# Xbee_shield.net
KiCad netlist of a schematic drawn in EAGLE
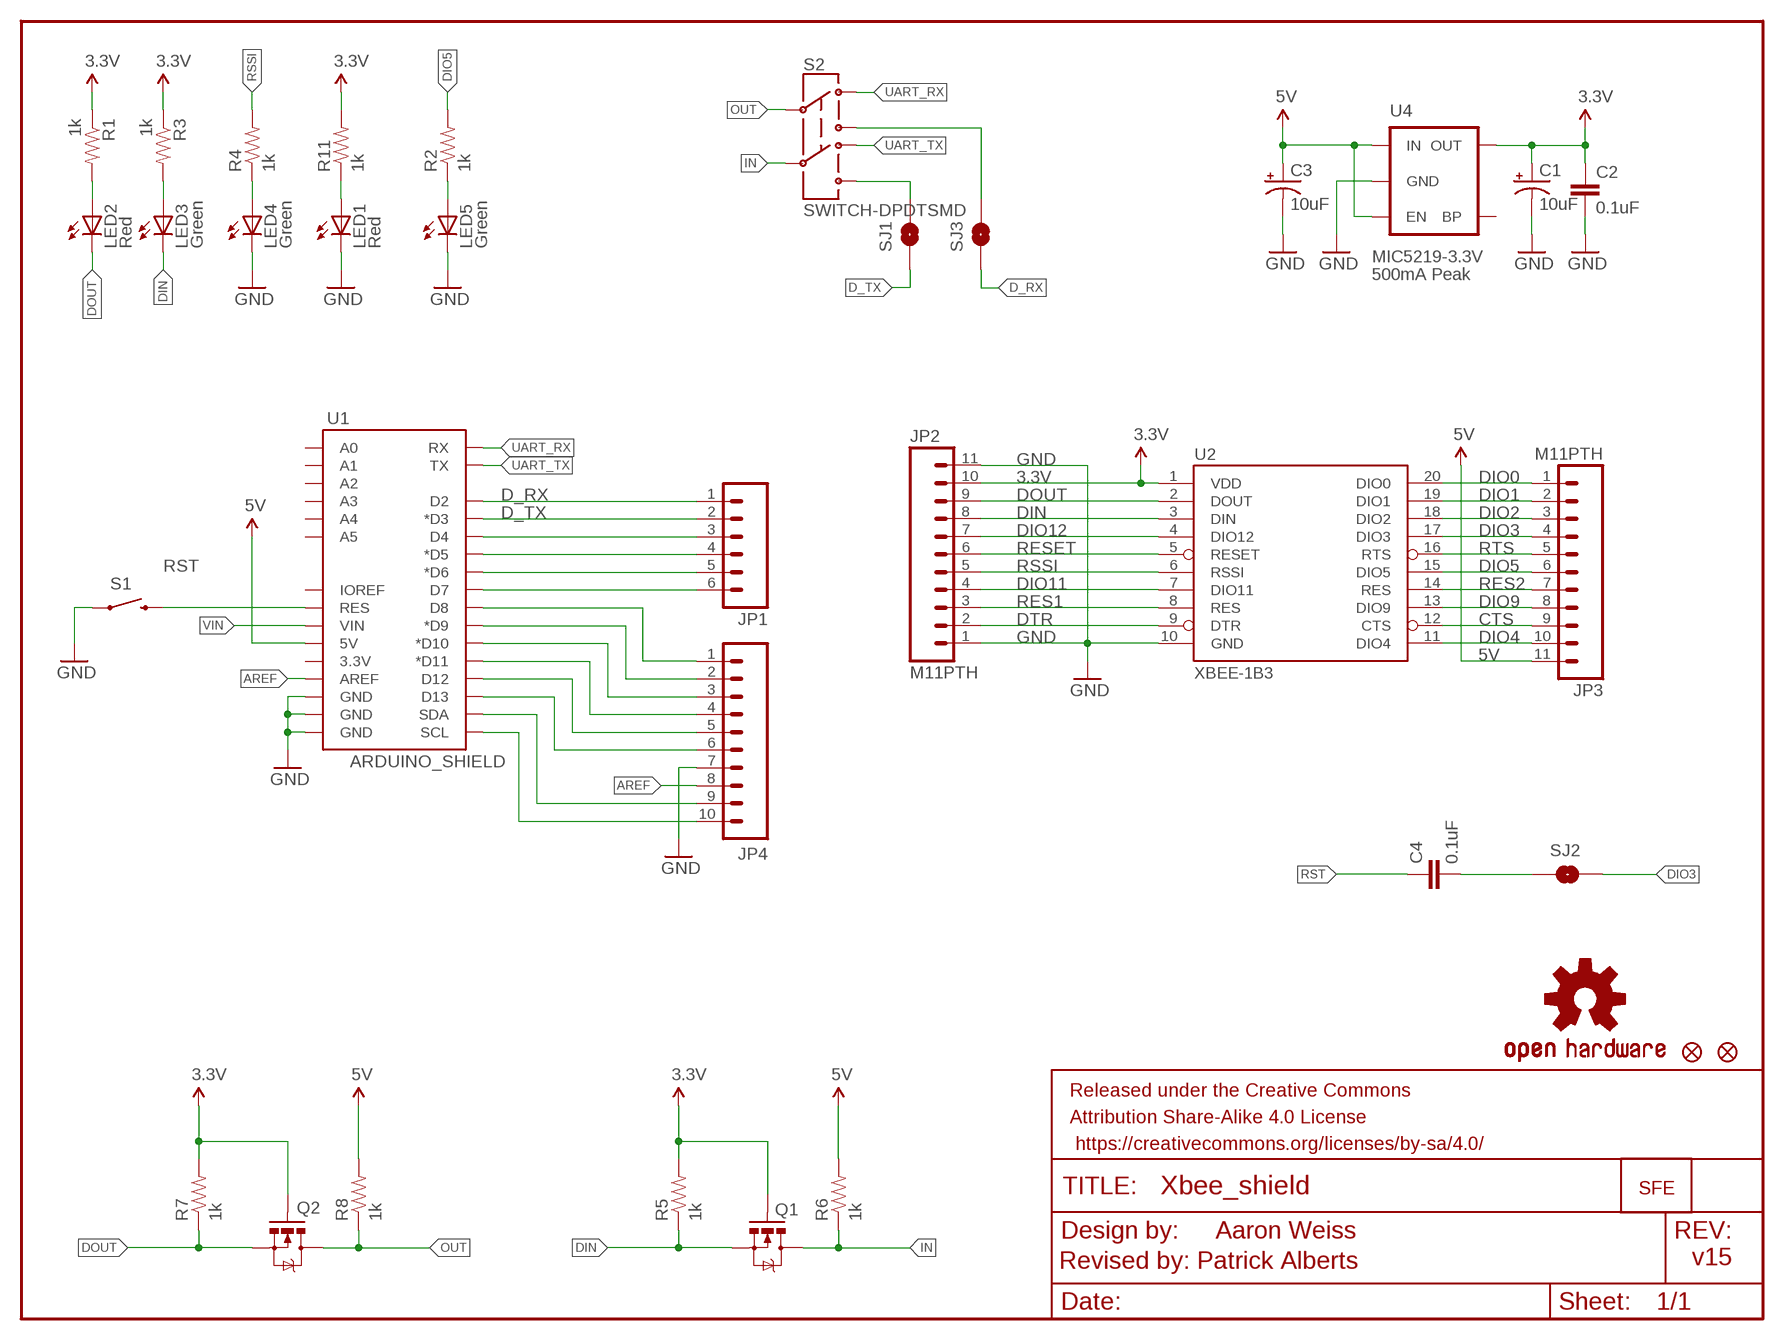
[diagram p0: schematic, sheet 1]

(export (version "E")
  (design (tool "Eeschema 10.0.6"))
  (components
    (comp (ref "C1")
      (value "10uF")
      (footprint "eagle-import:EIA3216")
      (libsource (lib "eagle-import") (part "CAP_POL1206"))
    )
    (comp (ref "C2")
      (value "0.1uF")
      (footprint "eagle-import:0603-CAP")
      (libsource (lib "eagle-import") (part "0.1UF-25V(+80/-20%)(0603)"))
    )
    (comp (ref "C3")
      (value "10uF")
      (footprint "eagle-import:EIA3216")
      (libsource (lib "eagle-import") (part "CAP_POL1206"))
    )
    (comp (ref "C4")
      (value "0.1uF")
      (footprint "eagle-import:0603-CAP")
      (libsource (lib "eagle-import") (part "0.1UF-25V(+80/-20%)(0603)"))
    )
    (comp (ref "FRAME1")
      (value "FRAME-LETTER")
      (footprint "eagle-import:CREATIVE_COMMONS")
      (libsource (lib "eagle-import") (part "FRAME-LETTER"))
    )
    (comp (ref "JP1")
      (value "M06SIP")
      (footprint "eagle-import:1X06")
      (libsource (lib "eagle-import") (part "M06SIP"))
    )
    (comp (ref "JP2")
      (value "M11PTH")
      (footprint "eagle-import:1X11")
      (libsource (lib "eagle-import") (part "M11PTH"))
    )
    (comp (ref "JP3")
      (value "M11PTH")
      (footprint "eagle-import:1X11")
      (libsource (lib "eagle-import") (part "M11PTH"))
    )
    (comp (ref "JP4")
      (value "M10\"")
      (footprint "eagle-import:1X10")
      (libsource (lib "eagle-import") (part "M10{dblquote}"))
    )
    (comp (ref "JP5")
      (value "FIDUCIAL1X2")
      (footprint "eagle-import:FIDUCIAL-1X2")
      (libsource (lib "eagle-import") (part "FIDUCIAL1X2"))
    )
    (comp (ref "JP6")
      (value "FIDUCIAL1X2")
      (footprint "eagle-import:FIDUCIAL-1X2")
      (libsource (lib "eagle-import") (part "FIDUCIAL1X2"))
    )
    (comp (ref "JP7")
      (value "LOGO-SFENEW")
      (footprint "eagle-import:SFE-NEW-WEBLOGO")
      (libsource (lib "eagle-import") (part "LOGO-SFENEW"))
    )
    (comp (ref "LED1")
      (value "Red")
      (footprint "eagle-import:LED-0603")
      (libsource (lib "eagle-import") (part "LED-RED0603"))
    )
    (comp (ref "LED2")
      (value "Red")
      (footprint "eagle-import:LED-0603")
      (libsource (lib "eagle-import") (part "LED-RED0603"))
    )
    (comp (ref "LED3")
      (value "Green")
      (footprint "eagle-import:LED-0603")
      (libsource (lib "eagle-import") (part "LED-GREEN0603"))
    )
    (comp (ref "LED4")
      (value "Green")
      (footprint "eagle-import:LED-0603")
      (libsource (lib "eagle-import") (part "LED-GREEN0603"))
    )
    (comp (ref "LED5")
      (value "Green")
      (footprint "eagle-import:LED-0603")
      (libsource (lib "eagle-import") (part "LED-GREEN0603"))
    )
    (comp (ref "Q1")
      (value "MOSFET-NCHANNELSMD")
      (footprint "eagle-import:SOT23-3")
      (libsource (lib "eagle-import") (part "MOSFET-NCHANNELSMD"))
    )
    (comp (ref "Q2")
      (value "MOSFET-NCHANNELSMD")
      (footprint "eagle-import:SOT23-3")
      (libsource (lib "eagle-import") (part "MOSFET-NCHANNELSMD"))
    )
    (comp (ref "R1")
      (value "1k")
      (footprint "eagle-import:0603-RES")
      (libsource (lib "eagle-import") (part "1KOHM1/10W1%(0603)"))
    )
    (comp (ref "R2")
      (value "1k")
      (footprint "eagle-import:0603-RES")
      (libsource (lib "eagle-import") (part "1KOHM1/10W1%(0603)"))
    )
    (comp (ref "R3")
      (value "1k")
      (footprint "eagle-import:0603-RES")
      (libsource (lib "eagle-import") (part "1KOHM1/10W1%(0603)"))
    )
    (comp (ref "R4")
      (value "1k")
      (footprint "eagle-import:0603-RES")
      (libsource (lib "eagle-import") (part "1KOHM1/10W1%(0603)"))
    )
    (comp (ref "R5")
      (value "1k")
      (footprint "eagle-import:0603-RES")
      (libsource (lib "eagle-import") (part "1KOHM1/10W1%(0603)"))
    )
    (comp (ref "R6")
      (value "1k")
      (footprint "eagle-import:0603-RES")
      (libsource (lib "eagle-import") (part "1KOHM1/10W1%(0603)"))
    )
    (comp (ref "R7")
      (value "1k")
      (footprint "eagle-import:0603-RES")
      (libsource (lib "eagle-import") (part "1KOHM1/10W1%(0603)"))
    )
    (comp (ref "R8")
      (value "1k")
      (footprint "eagle-import:0603-RES")
      (libsource (lib "eagle-import") (part "1KOHM1/10W1%(0603)"))
    )
    (comp (ref "R11")
      (value "1k")
      (footprint "eagle-import:0603-RES")
      (libsource (lib "eagle-import") (part "1KOHM1/10W1%(0603)"))
    )
    (comp (ref "S1")
      (value "SWITCH-MOMENTARY-2SMD")
      (footprint "eagle-import:TACTILE_SWITCH_SMD")
      (libsource (lib "eagle-import") (part "SWITCH-MOMENTARY-2SMD"))
    )
    (comp (ref "S2")
      (value "SWITCH-DPDTSMD")
      (footprint "eagle-import:AYZ0202")
      (libsource (lib "eagle-import") (part "SWITCH-DPDTSMD"))
    )
    (comp (ref "SJ1")
      (value "D_TX")
      (footprint "eagle-import:SJ_2S")
      (libsource (lib "eagle-import") (part "SOLDERJUMPERNC"))
    )
    (comp (ref "SJ2")
      (value "SOLDERJUMPERTRACE")
      (footprint "eagle-import:SJ_2S-TRACE")
      (libsource (lib "eagle-import") (part "SOLDERJUMPERTRACE"))
    )
    (comp (ref "SJ3")
      (value "D_RX")
      (footprint "eagle-import:SJ_2S")
      (libsource (lib "eagle-import") (part "SOLDERJUMPERNC"))
    )
    (comp (ref "U$8")
      (value "OSHW-LOGOS")
      (footprint "eagle-import:OSHW-LOGO-S")
      (libsource (lib "eagle-import") (part "OSHW-LOGOS"))
    )
    (comp (ref "U1")
      (value "ARDUINO_SHIELD")
      (footprint "eagle-import:UNO_R3_SHIELD")
      (libsource (lib "eagle-import") (part "ARDUINO_R3_SHIELD"))
    )
    (comp (ref "U2")
      (value "XBEE-1B3")
      (footprint "eagle-import:XBEE-SMD")
      (libsource (lib "eagle-import") (part "XBEE-1B3"))
    )
    (comp (ref "U4")
      (value "V_REG_LDOSMD")
      (footprint "eagle-import:SOT23-5")
      (libsource (lib "eagle-import") (part "V_REG_LDOSMD"))
    )
  )
  (nets
    (net (code "1") (name "/CTS") (class "Default")
      (node (ref "JP3") (pin "9") (pinfunction "9_9") (pintype "passive"))
      (node (ref "U2") (pin "12") (pinfunction "CTS_12") (pintype "output"))
    )
    (net (code "2") (name "/DIO0") (class "Default")
      (node (ref "JP3") (pin "1") (pinfunction "1_1") (pintype "passive"))
      (node (ref "U2") (pin "20") (pinfunction "DIO0_20") (pintype "bidirectional"))
    )
    (net (code "3") (name "/DIO1") (class "Default")
      (node (ref "JP3") (pin "2") (pinfunction "2_2") (pintype "passive"))
      (node (ref "U2") (pin "19") (pinfunction "DIO1_19") (pintype "bidirectional"))
    )
    (net (code "4") (name "/DIO2") (class "Default")
      (node (ref "JP3") (pin "3") (pinfunction "3_3") (pintype "passive"))
      (node (ref "U2") (pin "18") (pinfunction "DIO2_18") (pintype "bidirectional"))
    )
    (net (code "5") (name "/DIO4") (class "Default")
      (node (ref "JP3") (pin "10") (pinfunction "10_10") (pintype "passive"))
      (node (ref "U2") (pin "11") (pinfunction "DIO4_11") (pintype "bidirectional"))
    )
    (net (code "6") (name "/DIO9") (class "Default")
      (node (ref "JP3") (pin "8") (pinfunction "8_8") (pintype "passive"))
      (node (ref "U2") (pin "13") (pinfunction "DIO9_13") (pintype "bidirectional"))
    )
    (net (code "7") (name "/DIO11") (class "Default")
      (node (ref "JP2") (pin "4") (pinfunction "4_4") (pintype "passive"))
      (node (ref "U2") (pin "7") (pinfunction "DIO11_7") (pintype "bidirectional"))
    )
    (net (code "8") (name "/DIO12") (class "Default")
      (node (ref "JP2") (pin "7") (pinfunction "7_7") (pintype "passive"))
      (node (ref "U2") (pin "4") (pinfunction "DIO12_4") (pintype "bidirectional"))
    )
    (net (code "9") (name "/DTR") (class "Default")
      (node (ref "JP2") (pin "2") (pinfunction "2_2") (pintype "passive"))
      (node (ref "U2") (pin "9") (pinfunction "DTR_9") (pintype "bidirectional"))
    )
    (net (code "10") (name "/RES1") (class "Default")
      (node (ref "JP2") (pin "3") (pinfunction "3_3") (pintype "passive"))
      (node (ref "U2") (pin "8") (pinfunction "RES_8") (pintype "bidirectional"))
    )
    (net (code "11") (name "/RES2") (class "Default")
      (node (ref "JP3") (pin "7") (pinfunction "7_7") (pintype "passive"))
      (node (ref "U2") (pin "14") (pinfunction "RES_14") (pintype "bidirectional"))
    )
    (net (code "12") (name "/RESET") (class "Default")
      (node (ref "JP2") (pin "6") (pinfunction "6_6") (pintype "passive"))
      (node (ref "U2") (pin "5") (pinfunction "RESET_5") (pintype "input"))
    )
    (net (code "13") (name "/RTS") (class "Default")
      (node (ref "JP3") (pin "5") (pinfunction "5_5") (pintype "passive"))
      (node (ref "U2") (pin "16") (pinfunction "RTS_16") (pintype "input"))
    )
    (net (code "14") (name "3.3V") (class "Default")
      (node (ref "C1") (pin "A") (pinfunction "+_A") (pintype "passive"))
      (node (ref "C2") (pin "1") (pinfunction "1_1") (pintype "passive"))
      (node (ref "JP2") (pin "10") (pinfunction "10_10") (pintype "passive"))
      (node (ref "Q1") (pin "1") (pinfunction "G_1") (pintype "passive"))
      (node (ref "Q2") (pin "1") (pinfunction "G_1") (pintype "passive"))
      (node (ref "R1") (pin "1") (pinfunction "1_1") (pintype "passive"))
      (node (ref "R11") (pin "2") (pinfunction "2_2") (pintype "passive"))
      (node (ref "R3") (pin "1") (pinfunction "1_1") (pintype "passive"))
      (node (ref "R5") (pin "2") (pinfunction "2_2") (pintype "passive"))
      (node (ref "R7") (pin "2") (pinfunction "2_2") (pintype "passive"))
      (node (ref "U2") (pin "1") (pinfunction "VDD_1") (pintype "power_in"))
      (node (ref "U4") (pin "5") (pinfunction "OUT_5") (pintype "passive"))
    )
    (net (code "15") (name "5V") (class "Default")
      (node (ref "C3") (pin "A") (pinfunction "+_A") (pintype "passive"))
      (node (ref "JP3") (pin "11") (pinfunction "11_11") (pintype "passive"))
      (node (ref "R6") (pin "2") (pinfunction "2_2") (pintype "passive"))
      (node (ref "R8") (pin "2") (pinfunction "2_2") (pintype "passive"))
      (node (ref "U1") (pin "5V") (pinfunction "5V_5V") (pintype "bidirectional"))
      (node (ref "U4") (pin "1") (pinfunction "IN_1") (pintype "input"))
      (node (ref "U4") (pin "3") (pinfunction "EN_3") (pintype "input"))
    )
    (net (code "16") (name "AREF") (class "Default")
      (node (ref "JP4") (pin "8") (pinfunction "8_8") (pintype "passive"))
      (node (ref "U1") (pin "AREF") (pinfunction "AREF_AREF") (pintype "bidirectional"))
    )
    (net (code "17") (name "DIN") (class "Default")
      (node (ref "JP2") (pin "8") (pinfunction "8_8") (pintype "passive"))
      (node (ref "LED3") (pin "C") (pinfunction "C_C") (pintype "passive"))
      (node (ref "Q1") (pin "2") (pinfunction "S_2") (pintype "passive"))
      (node (ref "R5") (pin "1") (pinfunction "1_1") (pintype "passive"))
      (node (ref "U2") (pin "3") (pinfunction "DIN_3") (pintype "input"))
    )
    (net (code "18") (name "DIO3") (class "Default")
      (node (ref "JP3") (pin "4") (pinfunction "4_4") (pintype "passive"))
      (node (ref "SJ2") (pin "2") (pinfunction "2_2") (pintype "passive"))
      (node (ref "U2") (pin "17") (pinfunction "DIO3_17") (pintype "bidirectional"))
    )
    (net (code "19") (name "DIO5") (class "Default")
      (node (ref "JP3") (pin "6") (pinfunction "6_6") (pintype "passive"))
      (node (ref "R2") (pin "2") (pinfunction "2_2") (pintype "passive"))
      (node (ref "U2") (pin "15") (pinfunction "DIO5_15") (pintype "bidirectional"))
    )
    (net (code "20") (name "DOUT") (class "Default")
      (node (ref "JP2") (pin "9") (pinfunction "9_9") (pintype "passive"))
      (node (ref "LED2") (pin "C") (pinfunction "C_C") (pintype "passive"))
      (node (ref "Q2") (pin "2") (pinfunction "S_2") (pintype "passive"))
      (node (ref "R7") (pin "1") (pinfunction "1_1") (pintype "passive"))
      (node (ref "U2") (pin "2") (pinfunction "DOUT_2") (pintype "output"))
    )
    (net (code "21") (name "D_RX") (class "Default")
      (node (ref "JP1") (pin "1") (pinfunction "1_1") (pintype "passive"))
      (node (ref "SJ3") (pin "1") (pinfunction "1_1") (pintype "passive"))
      (node (ref "U1") (pin "D2") (pinfunction "D2_D2") (pintype "bidirectional"))
    )
    (net (code "22") (name "D_TX") (class "Default")
      (node (ref "JP1") (pin "2") (pinfunction "2_2") (pintype "passive"))
      (node (ref "SJ1") (pin "1") (pinfunction "1_1") (pintype "passive"))
      (node (ref "U1") (pin "D3") (pinfunction "*D3_D3") (pintype "bidirectional"))
    )
    (net (code "23") (name "GND") (class "Default")
      (node (ref "C1") (pin "C") (pinfunction "-_C") (pintype "passive"))
      (node (ref "C2") (pin "2") (pinfunction "2_2") (pintype "passive"))
      (node (ref "C3") (pin "C") (pinfunction "-_C") (pintype "passive"))
      (node (ref "JP2") (pin "1") (pinfunction "1_1") (pintype "passive"))
      (node (ref "JP2") (pin "11") (pinfunction "11_11") (pintype "passive"))
      (node (ref "JP4") (pin "7") (pinfunction "7_7") (pintype "passive"))
      (node (ref "LED1") (pin "C") (pinfunction "C_C") (pintype "passive"))
      (node (ref "LED4") (pin "C") (pinfunction "C_C") (pintype "passive"))
      (node (ref "LED5") (pin "C") (pinfunction "C_C") (pintype "passive"))
      (node (ref "S1") (pin "1") (pinfunction "1_1") (pintype "passive"))
      (node (ref "U1") (pin "GND@0") (pinfunction "GND_GND@0") (pintype "bidirectional"))
      (node (ref "U1") (pin "GND@1") (pinfunction "GND_GND@1") (pintype "bidirectional"))
      (node (ref "U1") (pin "GND@2") (pinfunction "GND_GND@2") (pintype "bidirectional"))
      (node (ref "U2") (pin "10") (pinfunction "GND_10") (pintype "power_in"))
      (node (ref "U4") (pin "2") (pinfunction "GND_2") (pintype "input"))
    )
    (net (code "24") (name "IN") (class "Default")
      (node (ref "Q1") (pin "3") (pinfunction "D_3") (pintype "passive"))
      (node (ref "R6") (pin "1") (pinfunction "1_1") (pintype "passive"))
      (node (ref "S2") (pin "5") (pinfunction "5_5") (pintype "bidirectional"))
    )
    (net (code "25") (name "Net-(C4-Pad2)") (class "Default")
      (node (ref "C4") (pin "2") (pinfunction "2_2") (pintype "passive"))
      (node (ref "SJ2") (pin "1") (pinfunction "1_1") (pintype "passive"))
    )
    (net (code "26") (name "Net-(JP1-Pad3)") (class "Default")
      (node (ref "JP1") (pin "3") (pinfunction "3_3") (pintype "passive"))
      (node (ref "U1") (pin "D4") (pinfunction "D4_D4") (pintype "bidirectional"))
    )
    (net (code "27") (name "Net-(JP1-Pad6)") (class "Default")
      (node (ref "JP1") (pin "6") (pinfunction "6_6") (pintype "passive"))
      (node (ref "U1") (pin "D7") (pinfunction "D7_D7") (pintype "bidirectional"))
    )
    (net (code "28") (name "Net-(JP4-Pad1)") (class "Default")
      (node (ref "JP4") (pin "1") (pinfunction "1_1") (pintype "passive"))
      (node (ref "U1") (pin "D8") (pinfunction "D8_D8") (pintype "bidirectional"))
    )
    (net (code "29") (name "Net-(JP4-Pad5)") (class "Default")
      (node (ref "JP4") (pin "5") (pinfunction "5_5") (pintype "passive"))
      (node (ref "U1") (pin "D12") (pinfunction "D12_D12") (pintype "bidirectional"))
    )
    (net (code "30") (name "Net-(JP4-Pad6)") (class "Default")
      (node (ref "JP4") (pin "6") (pinfunction "6_6") (pintype "passive"))
      (node (ref "U1") (pin "D13") (pinfunction "D13_D13") (pintype "bidirectional"))
    )
    (net (code "31") (name "Net-(JP4-Pad9)") (class "Default")
      (node (ref "JP4") (pin "9") (pinfunction "9_9") (pintype "passive"))
      (node (ref "U1") (pin "SDA") (pinfunction "SDA_SDA") (pintype "bidirectional"))
    )
    (net (code "32") (name "Net-(JP4-Pad10)") (class "Default")
      (node (ref "JP4") (pin "10") (pinfunction "10_10") (pintype "passive"))
      (node (ref "U1") (pin "SCL") (pinfunction "SCL_SCL") (pintype "bidirectional"))
    )
    (net (code "33") (name "Net-(LED1-PadA)") (class "Default")
      (node (ref "LED1") (pin "A") (pinfunction "A_A") (pintype "passive"))
      (node (ref "R11") (pin "1") (pinfunction "1_1") (pintype "passive"))
    )
    (net (code "34") (name "Net-(LED2-PadA)") (class "Default")
      (node (ref "LED2") (pin "A") (pinfunction "A_A") (pintype "passive"))
      (node (ref "R1") (pin "2") (pinfunction "2_2") (pintype "passive"))
    )
    (net (code "35") (name "Net-(LED3-PadA)") (class "Default")
      (node (ref "LED3") (pin "A") (pinfunction "A_A") (pintype "passive"))
      (node (ref "R3") (pin "2") (pinfunction "2_2") (pintype "passive"))
    )
    (net (code "36") (name "Net-(LED4-PadA)") (class "Default")
      (node (ref "LED4") (pin "A") (pinfunction "A_A") (pintype "passive"))
      (node (ref "R4") (pin "1") (pinfunction "1_1") (pintype "passive"))
    )
    (net (code "37") (name "Net-(LED5-PadA)") (class "Default")
      (node (ref "LED5") (pin "A") (pinfunction "A_A") (pintype "passive"))
      (node (ref "R2") (pin "1") (pinfunction "1_1") (pintype "passive"))
    )
    (net (code "38") (name "Net-(S2-Pad3)") (class "Default")
      (node (ref "S2") (pin "3") (pinfunction "3_3") (pintype "bidirectional"))
      (node (ref "SJ3") (pin "2") (pinfunction "2_2") (pintype "passive"))
    )
    (net (code "39") (name "Net-(S2-Pad6)") (class "Default")
      (node (ref "S2") (pin "6") (pinfunction "6_6") (pintype "bidirectional"))
      (node (ref "SJ1") (pin "2") (pinfunction "2_2") (pintype "passive"))
    )
    (net (code "40") (name "Net-(U1-*D5)") (class "Default")
      (node (ref "JP1") (pin "4") (pinfunction "4_4") (pintype "passive"))
      (node (ref "U1") (pin "D5") (pinfunction "*D5_D5") (pintype "bidirectional"))
    )
    (net (code "41") (name "Net-(U1-*D6)") (class "Default")
      (node (ref "JP1") (pin "5") (pinfunction "5_5") (pintype "passive"))
      (node (ref "U1") (pin "D6") (pinfunction "*D6_D6") (pintype "bidirectional"))
    )
    (net (code "42") (name "Net-(U1-*D9)") (class "Default")
      (node (ref "JP4") (pin "2") (pinfunction "2_2") (pintype "passive"))
      (node (ref "U1") (pin "D9") (pinfunction "*D9_D9") (pintype "bidirectional"))
    )
    (net (code "43") (name "Net-(U1-*D10)") (class "Default")
      (node (ref "JP4") (pin "3") (pinfunction "3_3") (pintype "passive"))
      (node (ref "U1") (pin "D10") (pinfunction "*D10_D10") (pintype "bidirectional"))
    )
    (net (code "44") (name "Net-(U1-*D11)") (class "Default")
      (node (ref "JP4") (pin "4") (pinfunction "4_4") (pintype "passive"))
      (node (ref "U1") (pin "D11") (pinfunction "*D11_D11") (pintype "bidirectional"))
    )
    (net (code "45") (name "OUT") (class "Default")
      (node (ref "Q2") (pin "3") (pinfunction "D_3") (pintype "passive"))
      (node (ref "R8") (pin "1") (pinfunction "1_1") (pintype "passive"))
      (node (ref "S2") (pin "2") (pinfunction "2_2") (pintype "bidirectional"))
    )
    (net (code "46") (name "RSSI") (class "Default")
      (node (ref "JP2") (pin "5") (pinfunction "5_5") (pintype "passive"))
      (node (ref "R4") (pin "2") (pinfunction "2_2") (pintype "passive"))
      (node (ref "U2") (pin "6") (pinfunction "RSSI_6") (pintype "bidirectional"))
    )
    (net (code "47") (name "RST") (class "Default")
      (node (ref "C4") (pin "1") (pinfunction "1_1") (pintype "passive"))
      (node (ref "S1") (pin "3") (pinfunction "2_3") (pintype "passive"))
      (node (ref "U1") (pin "RES") (pinfunction "RES_RES") (pintype "bidirectional"))
    )
    (net (code "48") (name "UART_RX") (class "Default")
      (node (ref "S2") (pin "1") (pinfunction "1_1") (pintype "bidirectional"))
      (node (ref "U1") (pin "RX") (pinfunction "RX_RX") (pintype "bidirectional"))
    )
    (net (code "49") (name "UART_TX") (class "Default")
      (node (ref "S2") (pin "4") (pinfunction "4_4") (pintype "bidirectional"))
      (node (ref "U1") (pin "TX") (pinfunction "TX_TX") (pintype "bidirectional"))
    )
    (net (code "50") (name "VIN") (class "Default")
      (node (ref "U1") (pin "VIN") (pinfunction "VIN_VIN") (pintype "bidirectional"))
    )
    (net (code "51") (name "unconnected-(U1-Pad3.3V)") (class "Default")
      (node (ref "U1") (pin "3.3V") (pinfunction "3.3V_3.3V") (pintype "bidirectional"))
    )
    (net (code "52") (name "unconnected-(U1-PadA0)") (class "Default")
      (node (ref "U1") (pin "A0") (pinfunction "A0_A0") (pintype "bidirectional"))
    )
    (net (code "53") (name "unconnected-(U1-PadA1)") (class "Default")
      (node (ref "U1") (pin "A1") (pinfunction "A1_A1") (pintype "bidirectional"))
    )
    (net (code "54") (name "unconnected-(U1-PadA2)") (class "Default")
      (node (ref "U1") (pin "A2") (pinfunction "A2_A2") (pintype "bidirectional"))
    )
    (net (code "55") (name "unconnected-(U1-PadA3)") (class "Default")
      (node (ref "U1") (pin "A3") (pinfunction "A3_A3") (pintype "bidirectional"))
    )
    (net (code "56") (name "unconnected-(U1-PadA4)") (class "Default")
      (node (ref "U1") (pin "A4") (pinfunction "A4_A4") (pintype "bidirectional"))
    )
    (net (code "57") (name "unconnected-(U1-PadA5)") (class "Default")
      (node (ref "U1") (pin "A5") (pinfunction "A5_A5") (pintype "bidirectional"))
    )
    (net (code "58") (name "unconnected-(U1-PadIOREF)") (class "Default")
      (node (ref "U1") (pin "IOREF") (pinfunction "IOREF_IOREF") (pintype "bidirectional"))
    )
    (net (code "59") (name "unconnected-(U4-BP-Pad4)") (class "Default")
      (node (ref "U4") (pin "4") (pinfunction "BP_4") (pintype "input"))
    )
  )
)
